# Ideal_Diode_Implementation.net
KiCad netlist of a schematic drawn in Altium Designer
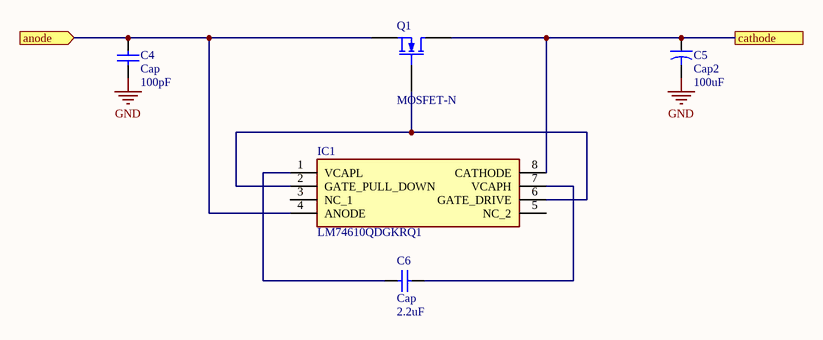
[diagram p0: Ideal Diode Implementation.SchDoc]

(export (version "E")
  (design (tool "Eeschema 10.0.6"))
  (components
    (comp (ref "C4")
      (value "Cap")
      (footprint "RAD-0.3")
      (description "Capacitor")
      (fields (field (name "ALTIUM_VALUE") "100pF") (field (name "PUBLISHER") "Altium Limited"))
      (libsource (lib "Miscellaneous Devices") (part "Cap"))
    )
    (comp (ref "C5")
      (value "Cap2")
      (footprint "CAPR5-4X5")
      (description "Capacitor")
      (fields (field (name "ALTIUM_VALUE") "100uF") (field (name "PUBLISHER") "Altium Limited"))
      (libsource (lib "Miscellaneous Devices") (part "Cap2"))
    )
    (comp (ref "C6")
      (value "Cap")
      (footprint "RAD-0.3")
      (description "Capacitor")
      (fields (field (name "ALTIUM_VALUE") "2.2uF") (field (name "PUBLISHER") "Altium Limited"))
      (libsource (lib "Miscellaneous Devices") (part "Cap"))
    )
    (comp (ref "IC1")
      (value "LM74610QDGKRQ1")
      (footprint "SamacSys:SOP65P490X110-8N")
      (description "Integrated Circuit")
      (fields (field (name "MOUSER PART NUMBER") "595-LM74610QDGKRQ1"))
      (libsource (lib "*") (part "LM74610QDGKRQ1"))
    )
    (comp (ref "Q1")
      (value "MOSFET-N")
      (footprint "E3")
      (description "N-Channel MOSFET")
      (fields (field (name "PUBLISHER") "Altium Limited"))
      (libsource (lib "Miscellaneous Devices") (part "MOSFET-N"))
    )
  )
  (nets
    (net (code "1") (name "/anode") (class "Default")
      (node (ref "C4") (pin "2") (pinfunction "2_2") (pintype "passive"))
      (node (ref "IC1") (pin "4") (pinfunction "ANODE_4") (pintype "passive"))
      (node (ref "Q1") (pin "3") (pinfunction "S_3") (pintype "passive"))
    )
    (net (code "2") (name "/cathode") (class "Default")
      (node (ref "C5") (pin "1") (pinfunction "1_1") (pintype "passive"))
      (node (ref "IC1") (pin "8") (pinfunction "CATHODE_8") (pintype "passive"))
      (node (ref "Q1") (pin "1") (pinfunction "D_1") (pintype "passive"))
    )
    (net (code "3") (name "GND") (class "Default")
      (node (ref "C4") (pin "1") (pinfunction "1_1") (pintype "passive"))
      (node (ref "C5") (pin "2") (pinfunction "2_2") (pintype "passive"))
    )
    (net (code "4") (name "Net-(IC1-GATE_DRIVE)") (class "Default")
      (node (ref "IC1") (pin "2") (pinfunction "GATE_PULL_DOWN_2") (pintype "passive"))
      (node (ref "IC1") (pin "6") (pinfunction "GATE_DRIVE_6") (pintype "passive"))
      (node (ref "Q1") (pin "2") (pinfunction "G_2") (pintype "passive"))
    )
    (net (code "5") (name "Net-(IC1-VCAPH)") (class "Default")
      (node (ref "C6") (pin "2") (pinfunction "2_2") (pintype "passive"))
      (node (ref "IC1") (pin "7") (pinfunction "VCAPH_7") (pintype "passive"))
    )
    (net (code "6") (name "Net-(IC1-VCAPL)") (class "Default")
      (node (ref "C6") (pin "1") (pinfunction "1_1") (pintype "passive"))
      (node (ref "IC1") (pin "1") (pinfunction "VCAPL_1") (pintype "passive"))
    )
    (net (code "7") (name "unconnected-(IC1-NC_1-Pad3)") (class "Default")
      (node (ref "IC1") (pin "3") (pinfunction "NC_1_3") (pintype "passive"))
    )
    (net (code "8") (name "unconnected-(IC1-NC_2-Pad5)") (class "Default")
      (node (ref "IC1") (pin "5") (pinfunction "NC_2_5") (pintype "passive"))
    )
  )
)
